# Rollator_2020-08-26_12-51-18.net
KiCad netlist of a schematic drawn in EasyEDA
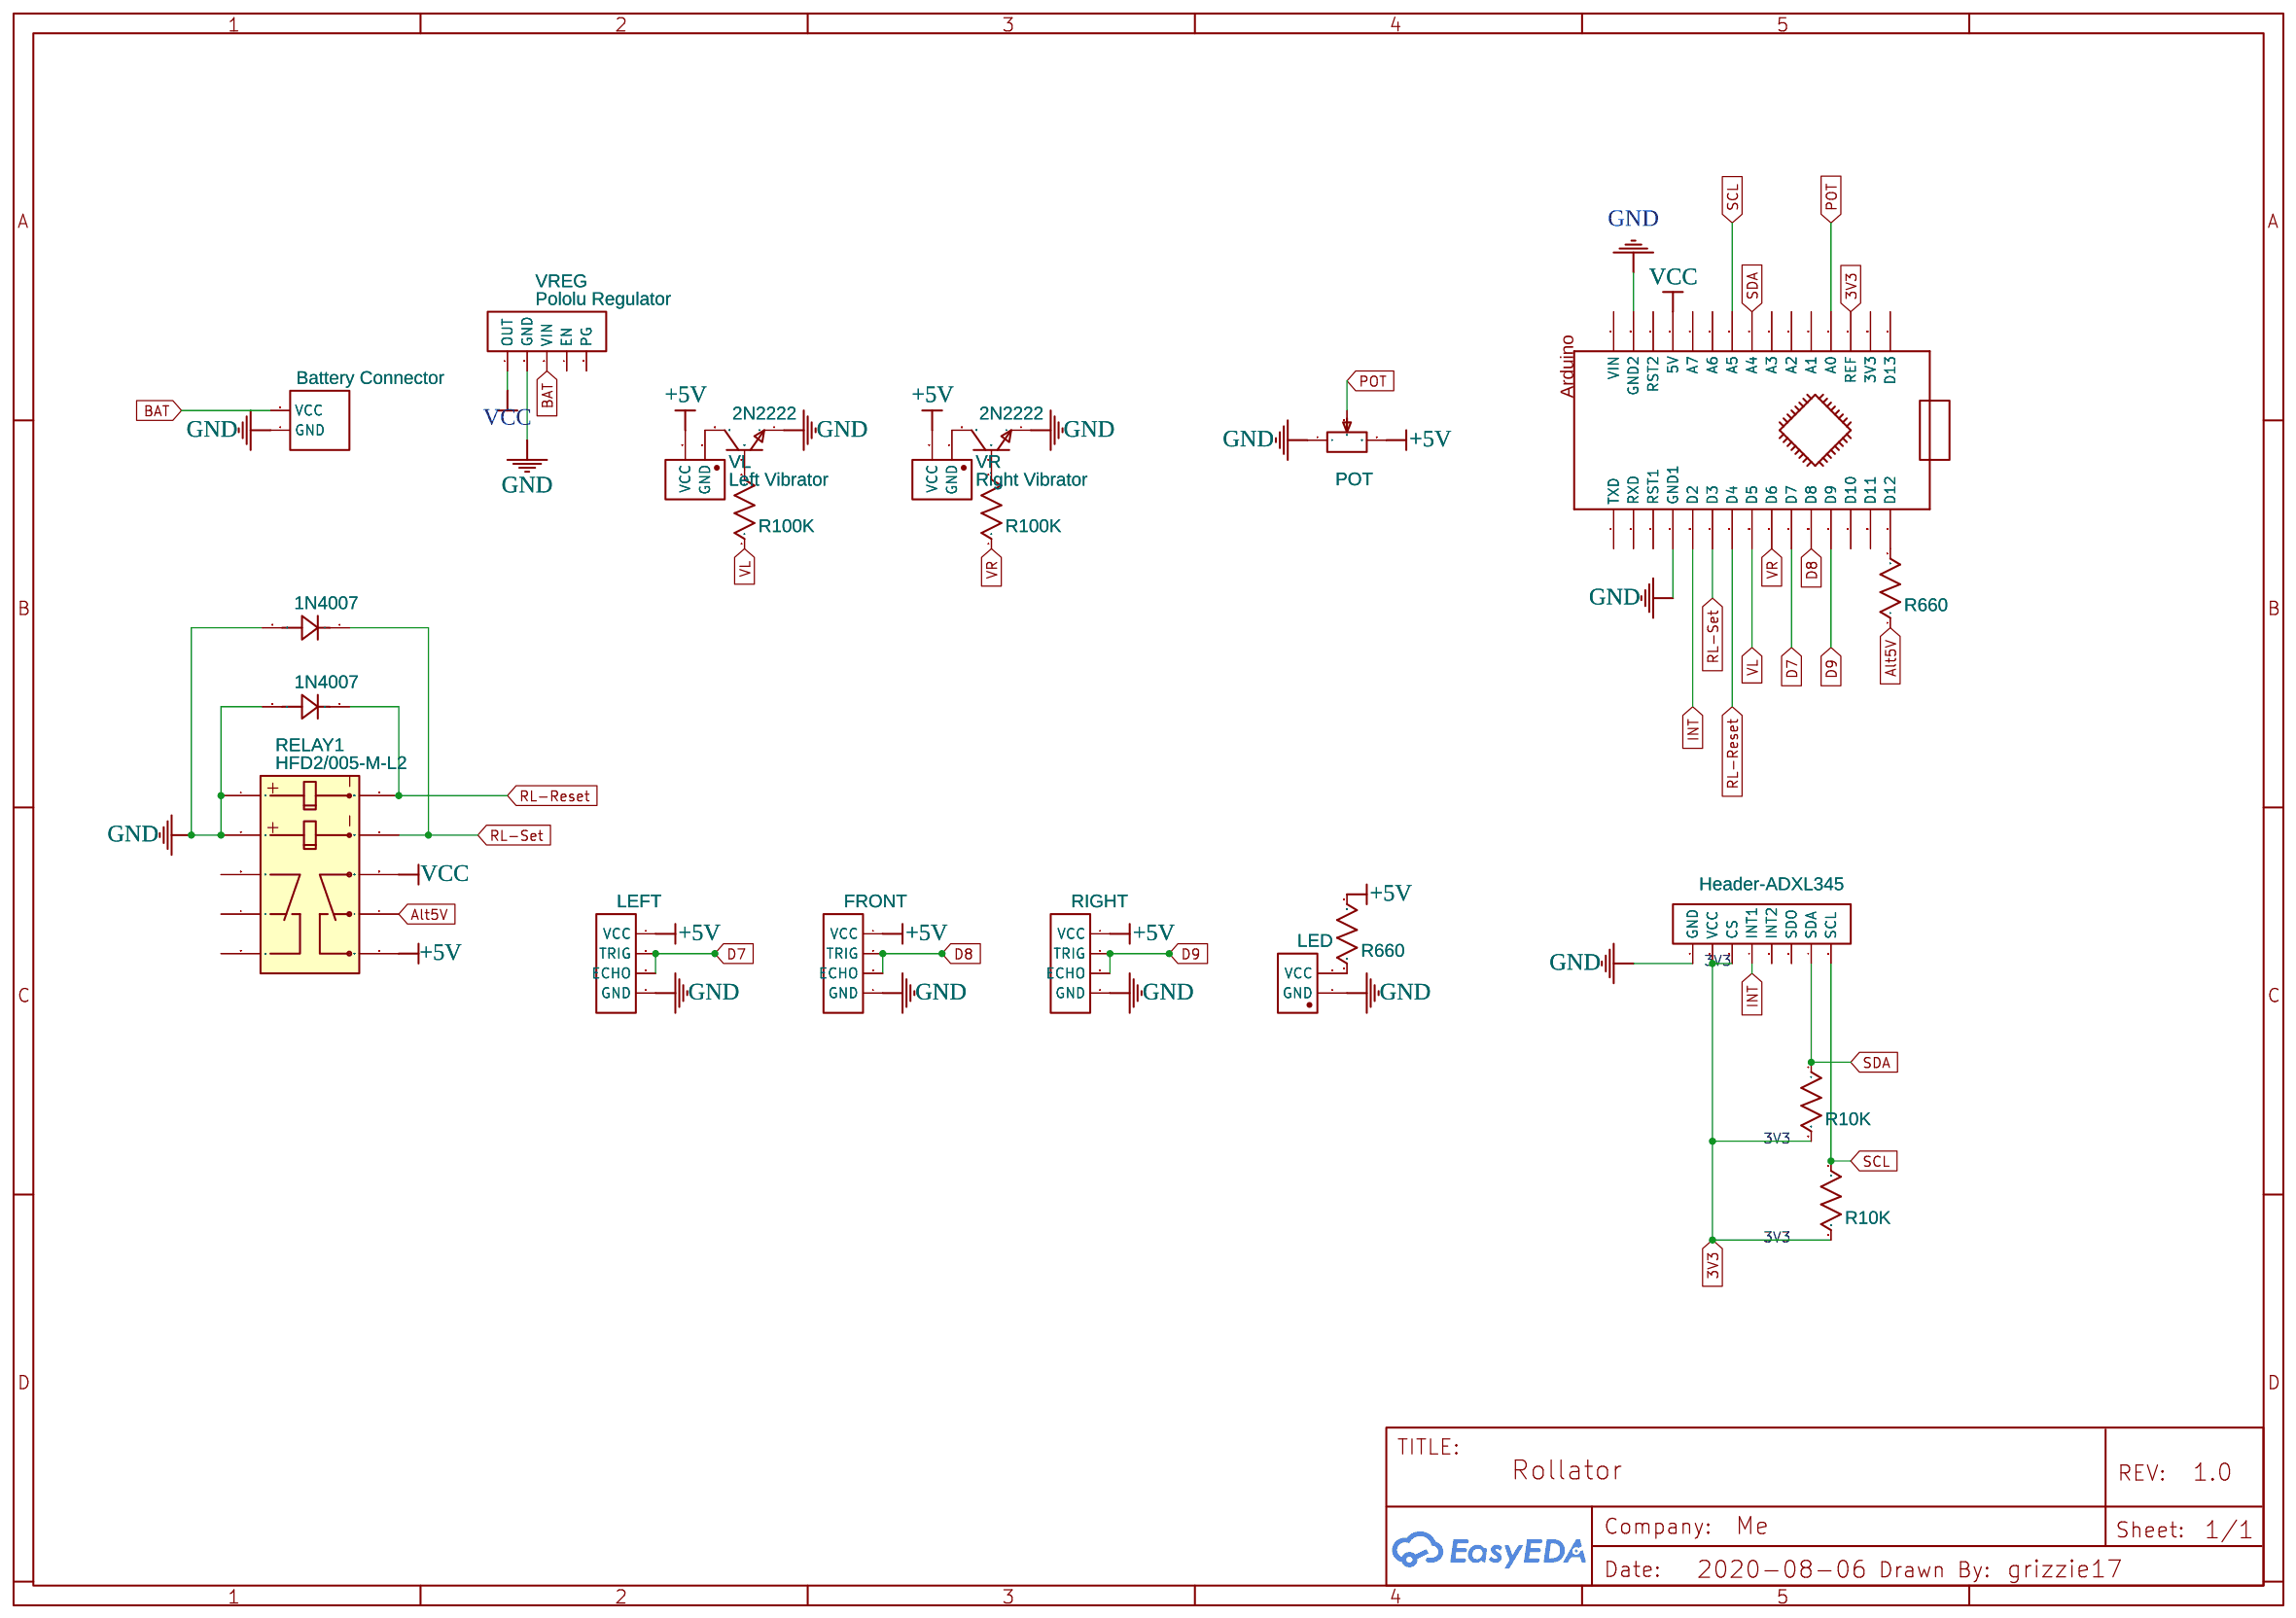
[diagram p0: schematic sheet]

(export (version "E")
  (design (tool "Eeschema 10.0.6"))
  (components
    (comp (ref "ACL")
      (value "Header-ADXL345")
      (fields
        (field (name "BOM_Manufacturer Part") "Female headerHDR1X8-2.54")
        (field (name "BOM_Supplier Part") "C27438")
      )
      (libsource (lib "") (part "Header-Female-2.54_1x8"))
    )
    (comp (ref "D1")
      (value "1N4007")
      (fields
        (field (name "BOM_Manufacturer Part") "1N4007G+ DIODE")
        (field (name "BOM_Supplier Part") "267-5047")
      )
      (libsource (lib "") (part "DIODE 1N4007"))
    )
    (comp (ref "D2")
      (value "1N4007")
      (fields
        (field (name "BOM_Manufacturer Part") "1N4007G+ DIODE")
        (field (name "BOM_Supplier Part") "267-5047")
      )
      (libsource (lib "") (part "DIODE 1N4007"))
    )
    (comp (ref "LED") (value "LED") (libsource (lib "") (part "Header_Female_1X2_2_54")))
    (comp (ref "P1")
      (value "LEFT")
      (fields
        (field (name "BOM_Manufacturer Part") "Header-Female-2.54_1x4")
        (field (name "BOM_Supplier Part") "C124413")
      )
      (libsource (lib "") (part "Header-Female-2.54_1x4"))
    )
    (comp (ref "P2")
      (value "FRONT")
      (fields
        (field (name "BOM_Manufacturer Part") "Header-Female-2.54_1x4")
        (field (name "BOM_Supplier Part") "C124413")
      )
      (libsource (lib "") (part "Header-Female-2.54_1x4"))
    )
    (comp (ref "P3")
      (value "RIGHT")
      (fields
        (field (name "BOM_Manufacturer Part") "Header-Female-2.54_1x4")
        (field (name "BOM_Supplier Part") "C124413")
      )
      (libsource (lib "") (part "Header-Female-2.54_1x4"))
    )
    (comp (ref "Q1")
      (value "2N2222")
      (fields (field (name "BOM_Supplier Part") "C118536"))
      (libsource (lib "") (part "2N2222"))
    )
    (comp (ref "Q2")
      (value "2N2222")
      (fields (field (name "BOM_Supplier Part") "C118536"))
      (libsource (lib "") (part "2N2222"))
    )
    (comp (ref "R3")
      (value "POT")
      (fields
        (field (name "BOM_Manufacturer Part") "3386P-1-202")
        (field (name "BOM_Supplier Part") "C330453")
      )
      (libsource (lib "") (part "3386P-1-202_C330453"))
    )
    (comp (ref "R10K-3") (value "R10K") (libsource (lib "") (part "100K")))
    (comp (ref "R10K-4") (value "R10K") (libsource (lib "") (part "100K")))
    (comp (ref "R100K-1") (value "R100K") (libsource (lib "") (part "100K_1")))
    (comp (ref "R100K-2") (value "R100K") (libsource (lib "") (part "100K_1")))
    (comp (ref "R660-1") (value "R660") (libsource (lib "") (part "100K_2")))
    (comp (ref "R660-2") (value "R660") (libsource (lib "") (part "100K_2")))
    (comp (ref "RELAY1")
      (value "HFD2/005-M-L2")
      (fields
        (field (name "BOM_Manufacturer Part") "HFD2/003-S-L2")
        (field (name "BOM_Supplier Part") "C69851")
      )
      (libsource (lib "") (part "HFD2/005-M-L2"))
    )
    (comp (ref "U3") (value "Battery Connector") (libsource (lib "") (part "Battery Connector")))
    (comp (ref "UC1")
      (value "Arduino_Nano_v3")
      (fields (field (name "BOM_Manufacturer Part") "arduino_nano1"))
      (libsource (lib "") (part "Arduino_Nano_v3"))
    )
    (comp (ref "VL") (value "Left Vibrator") (libsource (lib "") (part "Header_Female_1X2_2_54_1")))
    (comp (ref "VR") (value "Right Vibrator") (libsource (lib "") (part "Header_Female_1X2_2_54_2")))
    (comp (ref "VREG")
      (value "Pololu Regulator")
      (fields
        (field (name "BOM_Manufacturer Part") "2.54mm 1*5p Female header")
        (field (name "BOM_Supplier Part") "C50950")
      )
      (libsource (lib "") (part "Header-Female-2.54_1x5"))
    )
  )
  (nets
    (net (code "1") (name "+5V") (class "Default")
      (node (ref "P1") (pin "4") (pinfunction "VCC_4") (pintype "passive"))
      (node (ref "P2") (pin "4") (pinfunction "VCC_4") (pintype "passive"))
      (node (ref "P3") (pin "4") (pinfunction "VCC_4") (pintype "passive"))
      (node (ref "R3") (pin "3") (pinfunction "3_3") (pintype "input"))
      (node (ref "R660-1") (pin "2") (pinfunction "2_2") (pintype "unspecified"))
      (node (ref "RELAY1") (pin "6") (pinfunction "6_6") (pintype "input"))
      (node (ref "VL") (pin "2") (pinfunction "VCC_2") (pintype "passive"))
      (node (ref "VR") (pin "2") (pinfunction "VCC_2") (pintype "passive"))
    )
    (net (code "2") (name "3V3") (class "Default")
      (node (ref "ACL") (pin "2") (pinfunction "VCC_2") (pintype "passive"))
      (node (ref "ACL") (pin "3") (pinfunction "CS_3") (pintype "input"))
      (node (ref "R10K-3") (pin "2") (pinfunction "2_2") (pintype "unspecified"))
      (node (ref "R10K-4") (pin "2") (pinfunction "2_2") (pintype "unspecified"))
      (node (ref "UC1") (pin "REF") (pinfunction "REF_REF") (pintype "unspecified"))
    )
    (net (code "3") (name "Alt5V") (class "Default")
      (node (ref "R660-2") (pin "1") (pinfunction "1_1") (pintype "unspecified"))
      (node (ref "RELAY1") (pin "7") (pinfunction "7_7") (pintype "input"))
    )
    (net (code "4") (name "BAT") (class "Default")
      (node (ref "U3") (pin "2") (pinfunction "VCC_2") (pintype "passive"))
      (node (ref "VREG") (pin "3") (pinfunction "VIN_3") (pintype "passive"))
    )
    (net (code "5") (name "D7") (class "Default")
      (node (ref "P1") (pin "2") (pinfunction "ECHO_2") (pintype "output"))
      (node (ref "P1") (pin "3") (pinfunction "TRIG_3") (pintype "input"))
      (node (ref "UC1") (pin "D7") (pinfunction "D7_D7") (pintype "unspecified"))
    )
    (net (code "6") (name "D8") (class "Default")
      (node (ref "P2") (pin "2") (pinfunction "ECHO_2") (pintype "output"))
      (node (ref "P2") (pin "3") (pinfunction "TRIG_3") (pintype "input"))
      (node (ref "UC1") (pin "D8") (pinfunction "D8_D8") (pintype "unspecified"))
    )
    (net (code "7") (name "D9") (class "Default")
      (node (ref "P3") (pin "2") (pinfunction "ECHO_2") (pintype "output"))
      (node (ref "P3") (pin "3") (pinfunction "TRIG_3") (pintype "input"))
      (node (ref "UC1") (pin "D9") (pinfunction "D9_D9") (pintype "unspecified"))
    )
    (net (code "8") (name "GND") (class "Default")
      (node (ref "ACL") (pin "1") (pinfunction "GND_1") (pintype "passive"))
      (node (ref "D1") (pin "2") (pinfunction "2_2") (pintype "unspecified"))
      (node (ref "D2") (pin "2") (pinfunction "2_2") (pintype "unspecified"))
      (node (ref "LED") (pin "1") (pinfunction "GND_1") (pintype "passive"))
      (node (ref "P1") (pin "1") (pinfunction "GND_1") (pintype "passive"))
      (node (ref "P2") (pin "1") (pinfunction "GND_1") (pintype "passive"))
      (node (ref "P3") (pin "1") (pinfunction "GND_1") (pintype "passive"))
      (node (ref "Q1") (pin "1") (pinfunction "E_1") (pintype "unspecified"))
      (node (ref "Q2") (pin "1") (pinfunction "E_1") (pintype "unspecified"))
      (node (ref "R3") (pin "1") (pinfunction "1_1") (pintype "input"))
      (node (ref "RELAY1") (pin "1") (pinfunction "1_1") (pintype "input"))
      (node (ref "RELAY1") (pin "2") (pinfunction "2_2") (pintype "input"))
      (node (ref "U3") (pin "1") (pinfunction "GND_1") (pintype "passive"))
      (node (ref "UC1") (pin "GND1") (pinfunction "GND1_GND1") (pintype "unspecified"))
      (node (ref "UC1") (pin "GND2") (pinfunction "GND2_GND2") (pintype "unspecified"))
      (node (ref "VREG") (pin "2") (pinfunction "GND_2") (pintype "passive"))
    )
    (net (code "9") (name "INT") (class "Default")
      (node (ref "ACL") (pin "4") (pinfunction "INT1_4") (pintype "output"))
      (node (ref "UC1") (pin "D2") (pinfunction "D2_D2") (pintype "unspecified"))
    )
    (net (code "10") (name "Net-(LED-VCC)") (class "Default")
      (node (ref "LED") (pin "2") (pinfunction "VCC_2") (pintype "passive"))
      (node (ref "R660-1") (pin "1") (pinfunction "1_1") (pintype "unspecified"))
    )
    (net (code "11") (name "Net-(Q1-B)") (class "Default")
      (node (ref "Q1") (pin "2") (pinfunction "B_2") (pintype "unspecified"))
      (node (ref "R100K-1") (pin "2") (pinfunction "2_2") (pintype "unspecified"))
    )
    (net (code "12") (name "Net-(Q1-C)") (class "Default")
      (node (ref "Q1") (pin "3") (pinfunction "C_3") (pintype "unspecified"))
      (node (ref "VL") (pin "1") (pinfunction "GND_1") (pintype "passive"))
    )
    (net (code "13") (name "Net-(Q2-B)") (class "Default")
      (node (ref "Q2") (pin "2") (pinfunction "B_2") (pintype "unspecified"))
      (node (ref "R100K-2") (pin "2") (pinfunction "2_2") (pintype "unspecified"))
    )
    (net (code "14") (name "Net-(Q2-C)") (class "Default")
      (node (ref "Q2") (pin "3") (pinfunction "C_3") (pintype "unspecified"))
      (node (ref "VR") (pin "1") (pinfunction "GND_1") (pintype "passive"))
    )
    (net (code "15") (name "Net-(R660-2-Pad2)") (class "Default")
      (node (ref "R660-2") (pin "2") (pinfunction "2_2") (pintype "unspecified"))
      (node (ref "UC1") (pin "D12") (pinfunction "D12_D12") (pintype "unspecified"))
    )
    (net (code "16") (name "POT") (class "Default")
      (node (ref "R3") (pin "2") (pinfunction "2_2") (pintype "input"))
      (node (ref "UC1") (pin "A0") (pinfunction "A0_A0") (pintype "unspecified"))
    )
    (net (code "17") (name "RL-Reset") (class "Default")
      (node (ref "D1") (pin "1") (pinfunction "1_1") (pintype "unspecified"))
      (node (ref "RELAY1") (pin "10") (pinfunction "10_10") (pintype "input"))
      (node (ref "UC1") (pin "D4") (pinfunction "D4_D4") (pintype "unspecified"))
    )
    (net (code "18") (name "RL-Set") (class "Default")
      (node (ref "D2") (pin "1") (pinfunction "1_1") (pintype "unspecified"))
      (node (ref "RELAY1") (pin "9") (pinfunction "9_9") (pintype "input"))
      (node (ref "UC1") (pin "D3") (pinfunction "D3_D3") (pintype "unspecified"))
    )
    (net (code "19") (name "SCL") (class "Default")
      (node (ref "ACL") (pin "8") (pinfunction "SCL_8") (pintype "bidirectional"))
      (node (ref "R10K-3") (pin "1") (pinfunction "1_1") (pintype "unspecified"))
      (node (ref "UC1") (pin "A5") (pinfunction "A5_A5") (pintype "unspecified"))
    )
    (net (code "20") (name "SDA") (class "Default")
      (node (ref "ACL") (pin "7") (pinfunction "SDA_7") (pintype "bidirectional"))
      (node (ref "R10K-4") (pin "1") (pinfunction "1_1") (pintype "unspecified"))
      (node (ref "UC1") (pin "A4") (pinfunction "A4_A4") (pintype "unspecified"))
    )
    (net (code "21") (name "VCC") (class "Default")
      (node (ref "RELAY1") (pin "8") (pinfunction "8_8") (pintype "input"))
      (node (ref "UC1") (pin "5V") (pinfunction "5V_5V") (pintype "unspecified"))
      (node (ref "VREG") (pin "1") (pinfunction "OUT_1") (pintype "passive"))
    )
    (net (code "22") (name "VL") (class "Default")
      (node (ref "R100K-1") (pin "1") (pinfunction "1_1") (pintype "unspecified"))
      (node (ref "UC1") (pin "D5") (pinfunction "D5_D5") (pintype "unspecified"))
    )
    (net (code "23") (name "VR") (class "Default")
      (node (ref "R100K-2") (pin "1") (pinfunction "1_1") (pintype "unspecified"))
      (node (ref "UC1") (pin "D6") (pinfunction "D6_D6") (pintype "unspecified"))
    )
    (net (code "24") (name "unconnected-(ACL-INT2-Pad5)") (class "Default")
      (node (ref "ACL") (pin "5") (pinfunction "INT2_5") (pintype "output"))
    )
    (net (code "25") (name "unconnected-(ACL-SDO-Pad6)") (class "Default")
      (node (ref "ACL") (pin "6") (pinfunction "SDO_6") (pintype "bidirectional"))
    )
    (net (code "26") (name "unconnected-(RELAY1-Pad3)") (class "Default")
      (node (ref "RELAY1") (pin "3") (pinfunction "3_3") (pintype "input"))
    )
    (net (code "27") (name "unconnected-(RELAY1-Pad4)") (class "Default")
      (node (ref "RELAY1") (pin "4") (pinfunction "4_4") (pintype "input"))
    )
    (net (code "28") (name "unconnected-(RELAY1-Pad5)") (class "Default")
      (node (ref "RELAY1") (pin "5") (pinfunction "5_5") (pintype "input"))
    )
    (net (code "29") (name "unconnected-(UC1-Pad3V3)") (class "Default")
      (node (ref "UC1") (pin "3V3") (pinfunction "3V3_3V3") (pintype "unspecified"))
    )
    (net (code "30") (name "unconnected-(UC1-PadA1)") (class "Default")
      (node (ref "UC1") (pin "A1") (pinfunction "A1_A1") (pintype "unspecified"))
    )
    (net (code "31") (name "unconnected-(UC1-PadA2)") (class "Default")
      (node (ref "UC1") (pin "A2") (pinfunction "A2_A2") (pintype "unspecified"))
    )
    (net (code "32") (name "unconnected-(UC1-PadA3)") (class "Default")
      (node (ref "UC1") (pin "A3") (pinfunction "A3_A3") (pintype "unspecified"))
    )
    (net (code "33") (name "unconnected-(UC1-PadA6)") (class "Default")
      (node (ref "UC1") (pin "A6") (pinfunction "A6_A6") (pintype "unspecified"))
    )
    (net (code "34") (name "unconnected-(UC1-PadA7)") (class "Default")
      (node (ref "UC1") (pin "A7") (pinfunction "A7_A7") (pintype "unspecified"))
    )
    (net (code "35") (name "unconnected-(UC1-PadD10)") (class "Default")
      (node (ref "UC1") (pin "D10") (pinfunction "D10_D10") (pintype "unspecified"))
    )
    (net (code "36") (name "unconnected-(UC1-PadD11)") (class "Default")
      (node (ref "UC1") (pin "D11") (pinfunction "D11_D11") (pintype "unspecified"))
    )
    (net (code "37") (name "unconnected-(UC1-PadD13)") (class "Default")
      (node (ref "UC1") (pin "D13") (pinfunction "D13_D13") (pintype "unspecified"))
    )
    (net (code "38") (name "unconnected-(UC1-PadRST1)") (class "Default")
      (node (ref "UC1") (pin "RST1") (pinfunction "RST1_RST1") (pintype "unspecified"))
    )
    (net (code "39") (name "unconnected-(UC1-PadRST2)") (class "Default")
      (node (ref "UC1") (pin "RST2") (pinfunction "RST2_RST2") (pintype "unspecified"))
    )
    (net (code "40") (name "unconnected-(UC1-PadVIN)") (class "Default")
      (node (ref "UC1") (pin "VIN") (pinfunction "VIN_VIN") (pintype "unspecified"))
    )
    (net (code "41") (name "unconnected-(UC1-RXD-PadRX)") (class "Default")
      (node (ref "UC1") (pin "RX") (pinfunction "RXD_RX") (pintype "unspecified"))
    )
    (net (code "42") (name "unconnected-(UC1-TXD-PadTX)") (class "Default")
      (node (ref "UC1") (pin "TX") (pinfunction "TXD_TX") (pintype "unspecified"))
    )
    (net (code "43") (name "unconnected-(VREG-EN-Pad4)") (class "Default")
      (node (ref "VREG") (pin "4") (pinfunction "EN_4") (pintype "bidirectional"))
    )
    (net (code "44") (name "unconnected-(VREG-PG-Pad5)") (class "Default")
      (node (ref "VREG") (pin "5") (pinfunction "PG_5") (pintype "unspecified"))
    )
  )
)
